# esp8266-01relayfababesp-12-conplanodemas.net
KiCad netlist of a schematic drawn in EAGLE
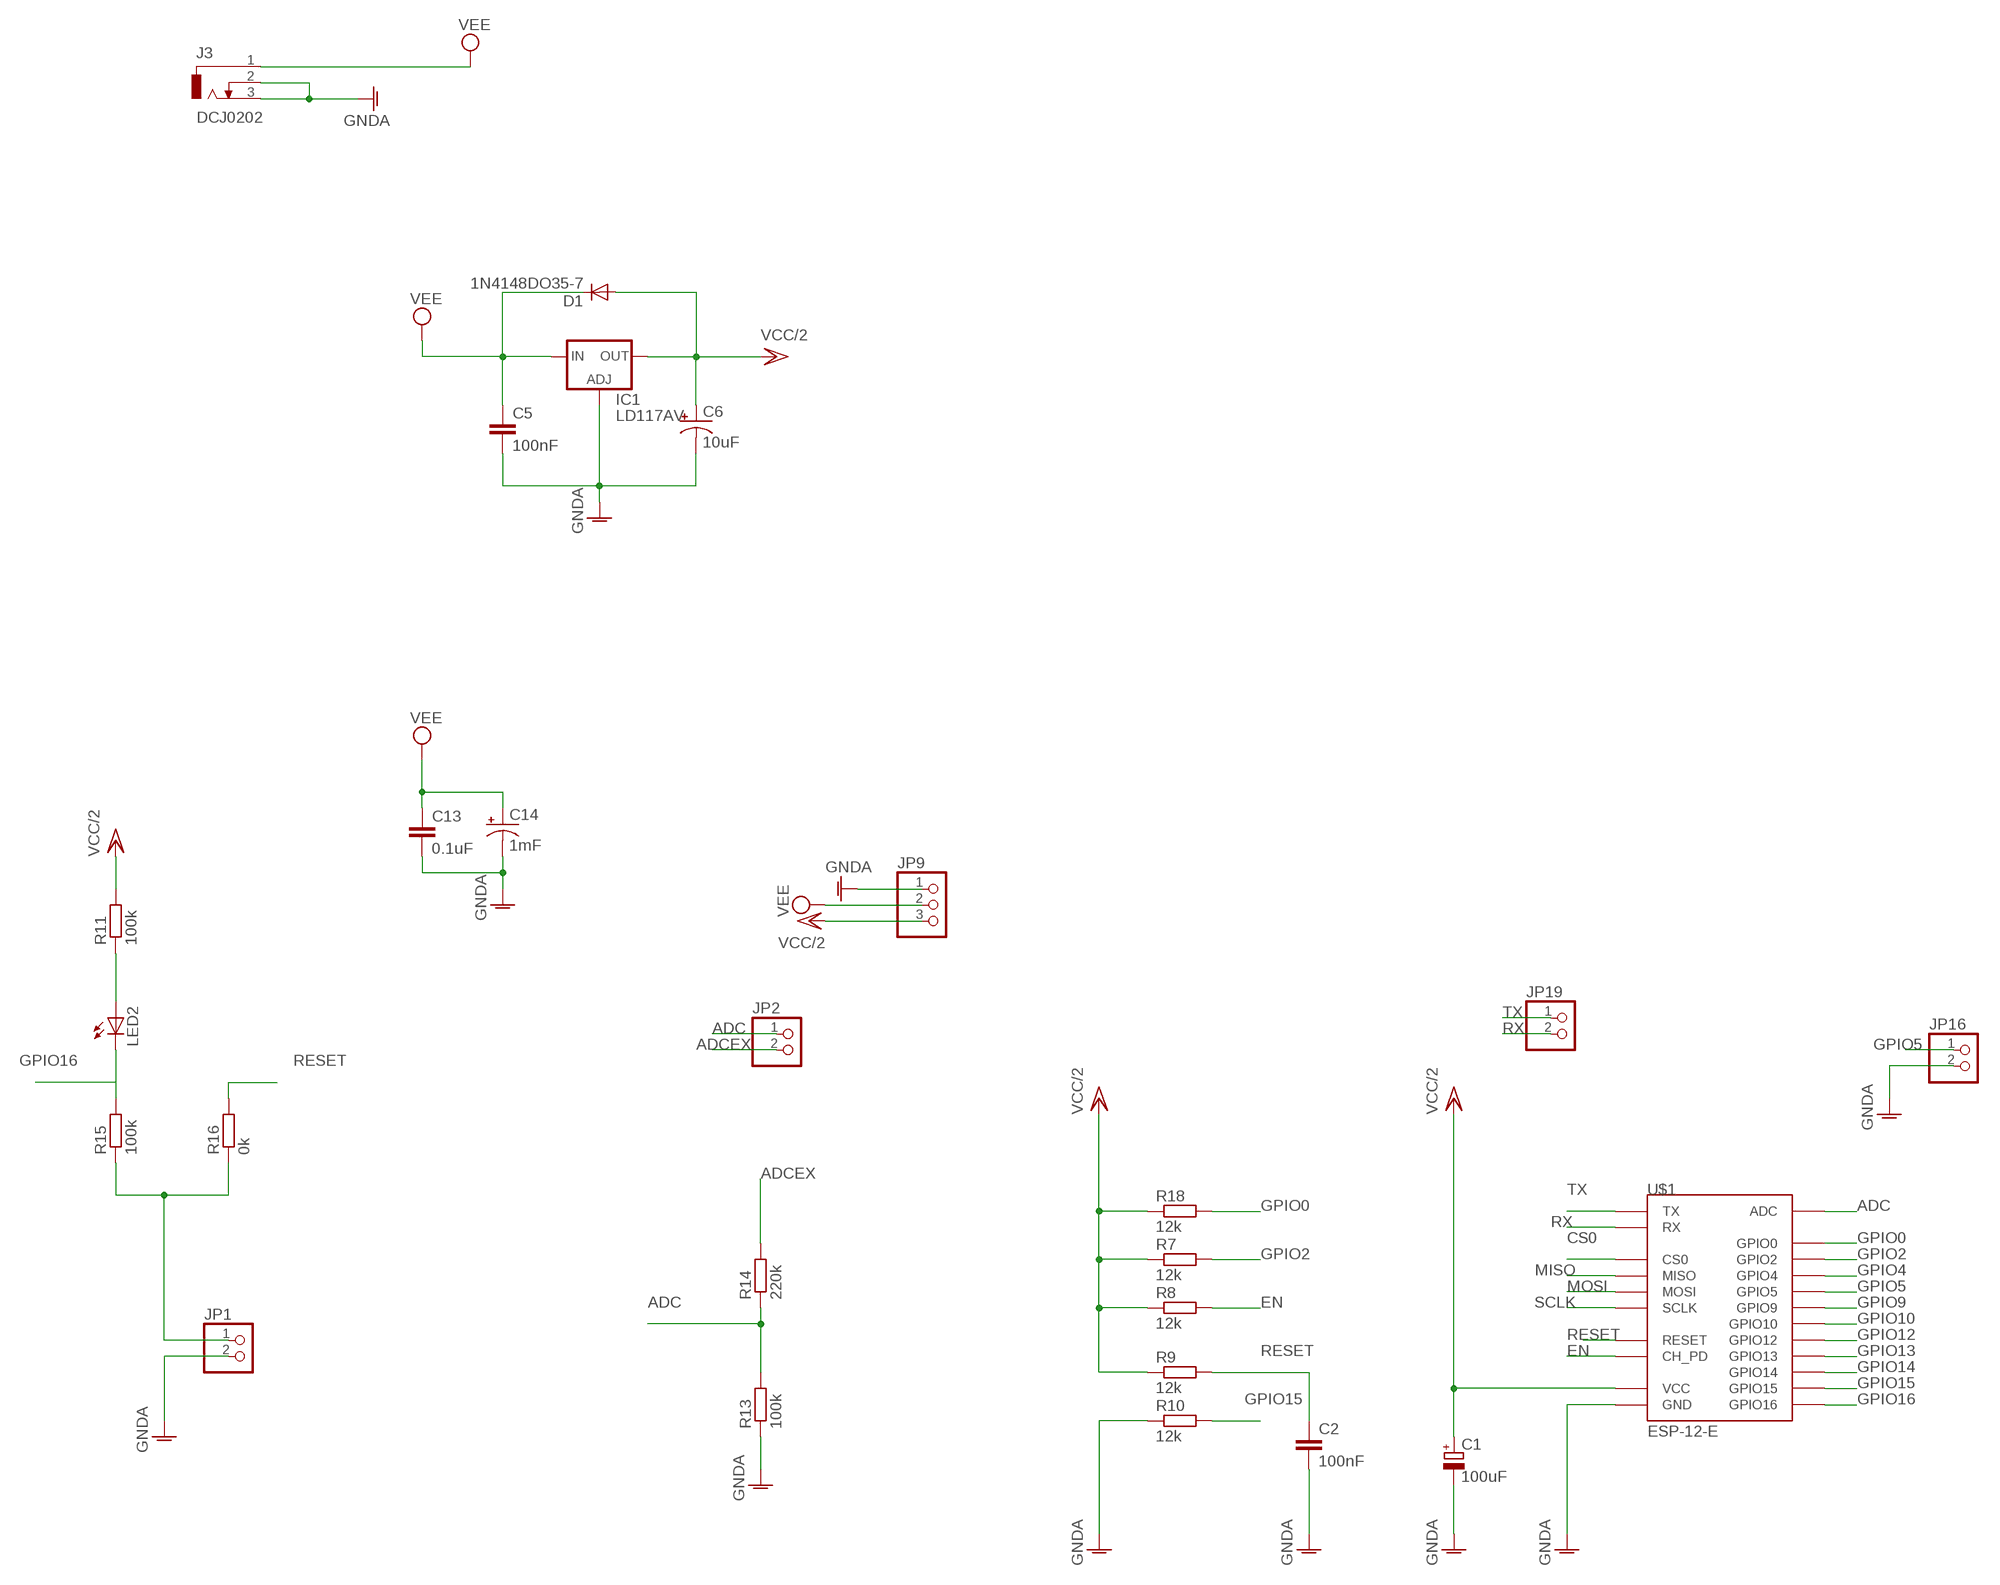
[diagram p0: schematic, sheet 1, part 1 of 2]
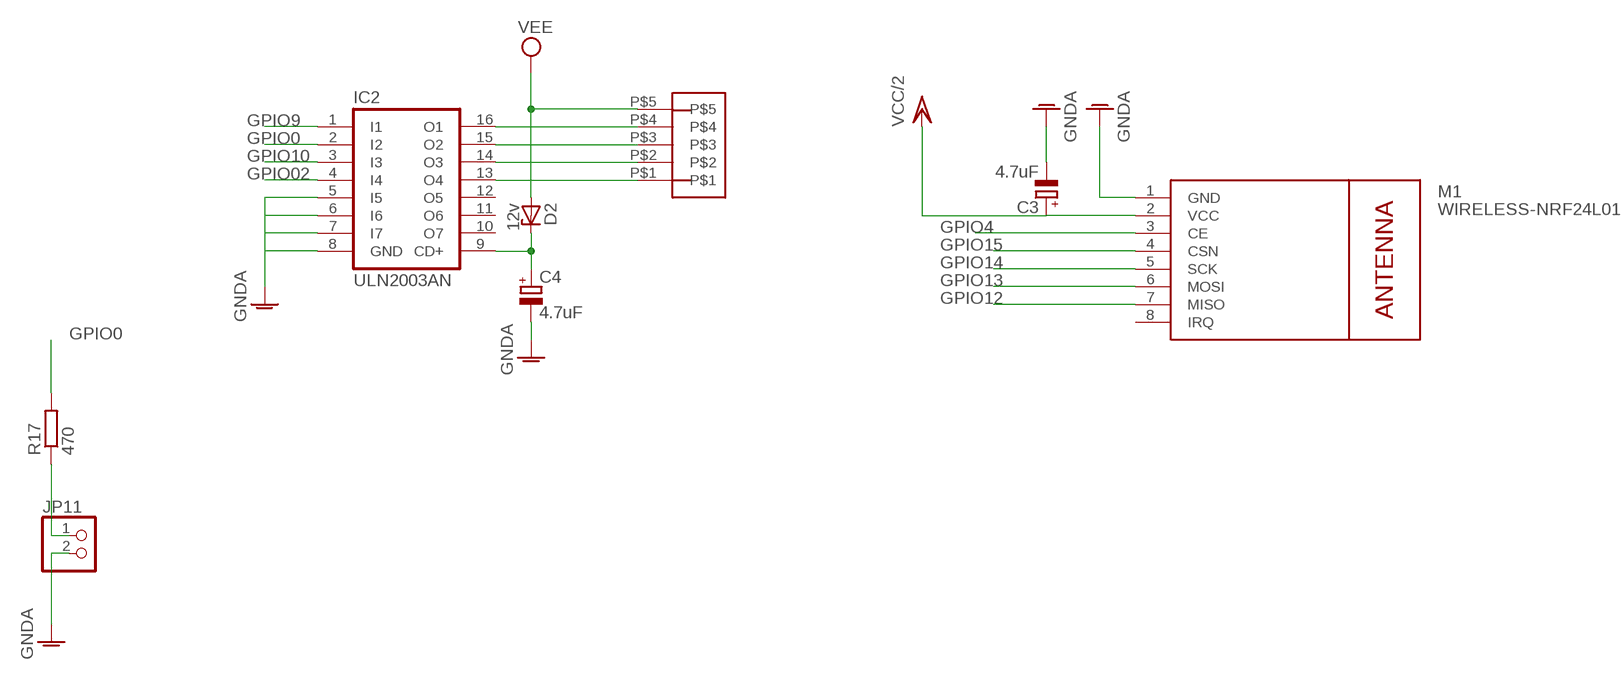
[diagram p1: schematic, sheet 1, part 2 of 2]

(export (version "E")
  (design (tool "Eeschema 10.0.6"))
  (components
    (comp (ref "C1")
      (value "100uF")
      (footprint "eagle-import:TT5D7")
      (libsource (lib "eagle-import") (part "CPOL-EUTT5D7"))
    )
    (comp (ref "C2")
      (value "100nF")
      (footprint "eagle-import:C025-024X044")
      (libsource (lib "eagle-import") (part "C-EU025-024X044"))
    )
    (comp (ref "C3")
      (value "4.7uF")
      (footprint "eagle-import:TT5D7")
      (libsource (lib "eagle-import") (part "CPOL-EUTT5D7"))
    )
    (comp (ref "C4")
      (value "4.7uF")
      (footprint "eagle-import:TT5D7")
      (libsource (lib "eagle-import") (part "CPOL-EUTT5D7"))
    )
    (comp (ref "C5")
      (value "100nF")
      (footprint "eagle-import:C025-025X050")
      (libsource (lib "eagle-import") (part "C-EU025-025X050"))
    )
    (comp (ref "C6")
      (value "10uF")
      (footprint "eagle-import:E2,5-6E")
      (libsource (lib "eagle-import") (part "CPOL-USE2,5-6E"))
    )
    (comp (ref "C13")
      (value "0.1uF")
      (footprint "eagle-import:C025-025X050")
      (libsource (lib "eagle-import") (part "C-EU025-025X050"))
    )
    (comp (ref "C14")
      (value "1mF")
      (footprint "eagle-import:E2,5-6E")
      (libsource (lib "eagle-import") (part "CPOL-USE2,5-6E"))
    )
    (comp (ref "D1")
      (value "1N4148DO35-7")
      (footprint "eagle-import:DO35-7")
      (libsource (lib "eagle-import") (part "1N4148DO35-7"))
    )
    (comp (ref "D2")
      (value "12v")
      (footprint "eagle-import:P1Z12")
      (libsource (lib "eagle-import") (part "ZENER-DIODEP1-12"))
    )
    (comp (ref "IC1")
      (value "LD117AV")
      (footprint "eagle-import:TO220L1")
      (libsource (lib "eagle-import") (part "LD117A?V"))
    )
    (comp (ref "IC2")
      (value "ULN2003AN")
      (footprint "eagle-import:DIL16")
      (libsource (lib "eagle-import") (part "ULN2003AN"))
    )
    (comp (ref "J3")
      (value "DCJ0202")
      (footprint "eagle-import:DCJ0202")
      (libsource (lib "eagle-import") (part "DCJ0202"))
    )
    (comp (ref "JP1")
      (value "PINHD-1X2")
      (footprint "eagle-import:1X02")
      (libsource (lib "eagle-import") (part "PINHD-1X2"))
    )
    (comp (ref "JP2")
      (value "PINHD-1X2")
      (footprint "eagle-import:1X02")
      (libsource (lib "eagle-import") (part "PINHD-1X2"))
    )
    (comp (ref "JP9")
      (value "PINHD-1X3")
      (footprint "eagle-import:1X03")
      (libsource (lib "eagle-import") (part "PINHD-1X3"))
    )
    (comp (ref "JP11")
      (value "PINHD-1X2")
      (footprint "eagle-import:1X02")
      (libsource (lib "eagle-import") (part "PINHD-1X2"))
    )
    (comp (ref "JP16")
      (value "PINHD-1X2")
      (footprint "eagle-import:1X02")
      (libsource (lib "eagle-import") (part "PINHD-1X2"))
    )
    (comp (ref "JP19")
      (value "PINHD-1X2")
      (footprint "eagle-import:1X02")
      (libsource (lib "eagle-import") (part "PINHD-1X2"))
    )
    (comp (ref "LED2")
      (value "LED3MM")
      (footprint "eagle-import:LED3MM")
      (libsource (lib "eagle-import") (part "LED3MM"))
    )
    (comp (ref "M1")
      (value "WIRELESS-NRF24L01")
      (footprint "eagle-import:WIRELESS-NRF24L01")
      (libsource (lib "eagle-import") (part "WIRELESS-NRF24L01"))
    )
    (comp (ref "R7")
      (value "12k")
      (footprint "eagle-import:0207_7")
      (libsource (lib "eagle-import") (part "R-EU_0207/7"))
    )
    (comp (ref "R8")
      (value "12k")
      (footprint "eagle-import:0207_7")
      (libsource (lib "eagle-import") (part "R-EU_0207/7"))
    )
    (comp (ref "R9")
      (value "12k")
      (footprint "eagle-import:0207_7")
      (libsource (lib "eagle-import") (part "R-EU_0207/7"))
    )
    (comp (ref "R10")
      (value "12k")
      (footprint "eagle-import:0207_7")
      (libsource (lib "eagle-import") (part "R-EU_0207/7"))
    )
    (comp (ref "R11")
      (value "100k")
      (footprint "eagle-import:0207_7")
      (libsource (lib "eagle-import") (part "R-EU_0207/7"))
    )
    (comp (ref "R13")
      (value "100k")
      (footprint "eagle-import:0207_7")
      (libsource (lib "eagle-import") (part "R-EU_0207/7"))
    )
    (comp (ref "R14")
      (value "220k")
      (footprint "eagle-import:0207_7")
      (libsource (lib "eagle-import") (part "R-EU_0207/7"))
    )
    (comp (ref "R15")
      (value "100k")
      (footprint "eagle-import:0207_7")
      (libsource (lib "eagle-import") (part "R-EU_0207/7"))
    )
    (comp (ref "R16")
      (value "0k")
      (footprint "eagle-import:0207_7")
      (libsource (lib "eagle-import") (part "R-EU_0207/7"))
    )
    (comp (ref "R17")
      (value "470")
      (footprint "eagle-import:0207_7")
      (libsource (lib "eagle-import") (part "R-EU_0207/7"))
    )
    (comp (ref "R18")
      (value "12k")
      (footprint "eagle-import:0207_7")
      (libsource (lib "eagle-import") (part "R-EU_0207/7"))
    )
    (comp (ref "U$1")
      (value "ESP-12-E")
      (footprint "eagle-import:ESP-12-E")
      (libsource (lib "eagle-import") (part "ESP-12-E"))
    )
    (comp (ref "U$3")
      (value "5_PIN_JST-XH")
      (footprint "eagle-import:5_PIN_JST-XH")
      (libsource (lib "eagle-import") (part "5_PIN_JST-XH"))
    )
  )
  (nets
    (net (code "1") (name "/ADC") (class "Default")
      (node (ref "JP2") (pin "1") (pinfunction "1_1") (pintype "passive"))
      (node (ref "R13") (pin "2") (pinfunction "2_2") (pintype "passive"))
      (node (ref "R14") (pin "1") (pinfunction "1_1") (pintype "passive"))
      (node (ref "U$1") (pin "ADC") (pinfunction "ADC_ADC") (pintype "bidirectional"))
    )
    (net (code "2") (name "/ADCEX") (class "Default")
      (node (ref "JP2") (pin "2") (pinfunction "2_2") (pintype "passive"))
      (node (ref "R14") (pin "2") (pinfunction "2_2") (pintype "passive"))
    )
    (net (code "3") (name "/CS0") (class "Default")
      (node (ref "U$1") (pin "CS0") (pinfunction "CS0_CS0") (pintype "bidirectional"))
    )
    (net (code "4") (name "/EN") (class "Default")
      (node (ref "R8") (pin "2") (pinfunction "2_2") (pintype "passive"))
      (node (ref "U$1") (pin "CH_PD") (pinfunction "CH_PD_CH_PD") (pintype "bidirectional"))
    )
    (net (code "5") (name "/GPIO0") (class "Default")
      (node (ref "IC2") (pin "2") (pinfunction "I2_2") (pintype "input"))
      (node (ref "R17") (pin "2") (pinfunction "2_2") (pintype "passive"))
      (node (ref "R18") (pin "2") (pinfunction "2_2") (pintype "passive"))
      (node (ref "U$1") (pin "GPIO0") (pinfunction "GPIO0_GPIO0") (pintype "bidirectional"))
    )
    (net (code "6") (name "/GPIO2") (class "Default")
      (node (ref "R7") (pin "2") (pinfunction "2_2") (pintype "passive"))
      (node (ref "U$1") (pin "GPIO2") (pinfunction "GPIO2_GPIO2") (pintype "bidirectional"))
    )
    (net (code "7") (name "/GPIO02") (class "Default")
      (node (ref "IC2") (pin "4") (pinfunction "I4_4") (pintype "input"))
    )
    (net (code "8") (name "/GPIO4") (class "Default")
      (node (ref "M1") (pin "3") (pinfunction "CE_3") (pintype "bidirectional"))
      (node (ref "U$1") (pin "GPIO4") (pinfunction "GPIO4_GPIO4") (pintype "bidirectional"))
    )
    (net (code "9") (name "/GPIO5") (class "Default")
      (node (ref "JP16") (pin "1") (pinfunction "1_1") (pintype "passive"))
      (node (ref "U$1") (pin "GPIO5") (pinfunction "GPIO5_GPIO5") (pintype "bidirectional"))
    )
    (net (code "10") (name "/GPIO9") (class "Default")
      (node (ref "IC2") (pin "1") (pinfunction "I1_1") (pintype "input"))
      (node (ref "U$1") (pin "GPIO9") (pinfunction "GPIO9_GPIO9") (pintype "bidirectional"))
    )
    (net (code "11") (name "/GPIO10") (class "Default")
      (node (ref "IC2") (pin "3") (pinfunction "I3_3") (pintype "input"))
      (node (ref "U$1") (pin "GPIO10") (pinfunction "GPIO10_GPIO10") (pintype "bidirectional"))
    )
    (net (code "12") (name "/GPIO12") (class "Default")
      (node (ref "M1") (pin "7") (pinfunction "MISO_7") (pintype "bidirectional"))
      (node (ref "U$1") (pin "GPIO12") (pinfunction "GPIO12_GPIO12") (pintype "bidirectional"))
    )
    (net (code "13") (name "/GPIO13") (class "Default")
      (node (ref "M1") (pin "6") (pinfunction "MOSI_6") (pintype "bidirectional"))
      (node (ref "U$1") (pin "GPIO13") (pinfunction "GPIO13_GPIO13") (pintype "bidirectional"))
    )
    (net (code "14") (name "/GPIO14") (class "Default")
      (node (ref "M1") (pin "5") (pinfunction "SCK_5") (pintype "bidirectional"))
      (node (ref "U$1") (pin "GPIO14") (pinfunction "GPIO14_GPIO14") (pintype "bidirectional"))
    )
    (net (code "15") (name "/GPIO15") (class "Default")
      (node (ref "M1") (pin "4") (pinfunction "CSN_4") (pintype "bidirectional"))
      (node (ref "R10") (pin "2") (pinfunction "2_2") (pintype "passive"))
      (node (ref "U$1") (pin "GPIO15") (pinfunction "GPIO15_GPIO15") (pintype "bidirectional"))
    )
    (net (code "16") (name "/GPIO16") (class "Default")
      (node (ref "LED2") (pin "K") (pinfunction "C_K") (pintype "passive"))
      (node (ref "R15") (pin "2") (pinfunction "2_2") (pintype "passive"))
      (node (ref "U$1") (pin "GPIO16") (pinfunction "GPIO16_GPIO16") (pintype "bidirectional"))
    )
    (net (code "17") (name "/MISO") (class "Default")
      (node (ref "U$1") (pin "MISO") (pinfunction "MISO_MISO") (pintype "bidirectional"))
    )
    (net (code "18") (name "/MOSI") (class "Default")
      (node (ref "U$1") (pin "MOSI") (pinfunction "MOSI_MOSI") (pintype "bidirectional"))
    )
    (net (code "19") (name "/RESET") (class "Default")
      (node (ref "C2") (pin "1") (pinfunction "1_1") (pintype "passive"))
      (node (ref "R16") (pin "2") (pinfunction "2_2") (pintype "passive"))
      (node (ref "R9") (pin "2") (pinfunction "2_2") (pintype "passive"))
      (node (ref "U$1") (pin "RESET") (pinfunction "RESET_RESET") (pintype "bidirectional"))
    )
    (net (code "20") (name "/RX") (class "Default")
      (node (ref "JP19") (pin "2") (pinfunction "2_2") (pintype "passive"))
      (node (ref "U$1") (pin "RX") (pinfunction "RX_RX") (pintype "bidirectional"))
    )
    (net (code "21") (name "/SCLK") (class "Default")
      (node (ref "U$1") (pin "SCLK") (pinfunction "SCLK_SCLK") (pintype "bidirectional"))
    )
    (net (code "22") (name "/TX") (class "Default")
      (node (ref "JP19") (pin "1") (pinfunction "1_1") (pintype "passive"))
      (node (ref "U$1") (pin "TX") (pinfunction "TX_TX") (pintype "bidirectional"))
    )
    (net (code "23") (name "GNDA") (class "Default")
      (node (ref "C1") (pin "-") (pinfunction "-_-") (pintype "passive"))
      (node (ref "C13") (pin "2") (pinfunction "2_2") (pintype "passive"))
      (node (ref "C14") (pin "-") (pinfunction "-_-") (pintype "passive"))
      (node (ref "C2") (pin "2") (pinfunction "2_2") (pintype "passive"))
      (node (ref "C3") (pin "-") (pinfunction "-_-") (pintype "passive"))
      (node (ref "C4") (pin "-") (pinfunction "-_-") (pintype "passive"))
      (node (ref "C5") (pin "2") (pinfunction "2_2") (pintype "passive"))
      (node (ref "C6") (pin "-") (pinfunction "-_-") (pintype "passive"))
      (node (ref "IC1") (pin "1") (pinfunction "ADJ_1") (pintype "input"))
      (node (ref "IC2") (pin "5") (pinfunction "I5_5") (pintype "input"))
      (node (ref "IC2") (pin "6") (pinfunction "I6_6") (pintype "input"))
      (node (ref "IC2") (pin "7") (pinfunction "I7_7") (pintype "input"))
      (node (ref "IC2") (pin "8") (pinfunction "GND_8") (pintype "power_in"))
      (node (ref "J3") (pin "2") (pinfunction "2_2") (pintype "passive"))
      (node (ref "J3") (pin "3") (pinfunction "3_3") (pintype "passive"))
      (node (ref "JP1") (pin "2") (pinfunction "2_2") (pintype "passive"))
      (node (ref "JP11") (pin "2") (pinfunction "2_2") (pintype "passive"))
      (node (ref "JP16") (pin "2") (pinfunction "2_2") (pintype "passive"))
      (node (ref "JP9") (pin "1") (pinfunction "1_1") (pintype "passive"))
      (node (ref "M1") (pin "1") (pinfunction "GND_1") (pintype "power_in"))
      (node (ref "R10") (pin "1") (pinfunction "1_1") (pintype "passive"))
      (node (ref "R13") (pin "1") (pinfunction "1_1") (pintype "passive"))
      (node (ref "U$1") (pin "GND") (pinfunction "GND_GND") (pintype "bidirectional"))
    )
    (net (code "24") (name "Net-(IC2-CD+)") (class "Default")
      (node (ref "C4") (pin "+") (pinfunction "+_+") (pintype "passive"))
      (node (ref "D2") (pin "C") (pinfunction "C_C") (pintype "passive"))
      (node (ref "IC2") (pin "9") (pinfunction "CD+_9") (pintype "passive"))
    )
    (net (code "25") (name "Net-(IC2-O1)") (class "Default")
      (node (ref "IC2") (pin "16") (pinfunction "O1_16") (pintype "open_collector"))
      (node (ref "U$3") (pin "P$4") (pinfunction "P$4_P$4") (pintype "bidirectional"))
    )
    (net (code "26") (name "Net-(IC2-O2)") (class "Default")
      (node (ref "IC2") (pin "15") (pinfunction "O2_15") (pintype "open_collector"))
      (node (ref "U$3") (pin "P$3") (pinfunction "P$3_P$3") (pintype "bidirectional"))
    )
    (net (code "27") (name "Net-(IC2-O3)") (class "Default")
      (node (ref "IC2") (pin "14") (pinfunction "O3_14") (pintype "open_collector"))
      (node (ref "U$3") (pin "P$2") (pinfunction "P$2_P$2") (pintype "bidirectional"))
    )
    (net (code "28") (name "Net-(IC2-O4)") (class "Default")
      (node (ref "IC2") (pin "13") (pinfunction "O4_13") (pintype "open_collector"))
      (node (ref "U$3") (pin "P$1") (pinfunction "P$1_P$1") (pintype "bidirectional"))
    )
    (net (code "29") (name "Net-(JP1-Pad1)") (class "Default")
      (node (ref "JP1") (pin "1") (pinfunction "1_1") (pintype "passive"))
      (node (ref "R15") (pin "1") (pinfunction "1_1") (pintype "passive"))
      (node (ref "R16") (pin "1") (pinfunction "1_1") (pintype "passive"))
    )
    (net (code "30") (name "Net-(JP11-Pad1)") (class "Default")
      (node (ref "JP11") (pin "1") (pinfunction "1_1") (pintype "passive"))
      (node (ref "R17") (pin "1") (pinfunction "1_1") (pintype "passive"))
    )
    (net (code "31") (name "Net-(LED2-PadA)") (class "Default")
      (node (ref "LED2") (pin "A") (pinfunction "A_A") (pintype "passive"))
      (node (ref "R11") (pin "1") (pinfunction "1_1") (pintype "passive"))
    )
    (net (code "32") (name "VCC{slash}2") (class "Default")
      (node (ref "C1") (pin "+") (pinfunction "+_+") (pintype "passive"))
      (node (ref "C3") (pin "+") (pinfunction "+_+") (pintype "passive"))
      (node (ref "C6") (pin "+") (pinfunction "+_+") (pintype "passive"))
      (node (ref "D1") (pin "A") (pinfunction "A_A") (pintype "passive"))
      (node (ref "IC1") (pin "2") (pinfunction "OUT_2") (pintype "passive"))
      (node (ref "JP9") (pin "3") (pinfunction "3_3") (pintype "passive"))
      (node (ref "M1") (pin "2") (pinfunction "VCC_2") (pintype "power_in"))
      (node (ref "R11") (pin "2") (pinfunction "2_2") (pintype "passive"))
      (node (ref "R18") (pin "1") (pinfunction "1_1") (pintype "passive"))
      (node (ref "R7") (pin "1") (pinfunction "1_1") (pintype "passive"))
      (node (ref "R8") (pin "1") (pinfunction "1_1") (pintype "passive"))
      (node (ref "R9") (pin "1") (pinfunction "1_1") (pintype "passive"))
      (node (ref "U$1") (pin "VCC") (pinfunction "VCC_VCC") (pintype "bidirectional"))
    )
    (net (code "33") (name "VEE") (class "Default")
      (node (ref "C13") (pin "1") (pinfunction "1_1") (pintype "passive"))
      (node (ref "C14") (pin "+") (pinfunction "+_+") (pintype "passive"))
      (node (ref "C5") (pin "1") (pinfunction "1_1") (pintype "passive"))
      (node (ref "D1") (pin "C") (pinfunction "C_C") (pintype "passive"))
      (node (ref "D2") (pin "A") (pinfunction "A_A") (pintype "passive"))
      (node (ref "IC1") (pin "3") (pinfunction "IN_3") (pintype "input"))
      (node (ref "J3") (pin "1") (pinfunction "1_1") (pintype "passive"))
      (node (ref "JP9") (pin "2") (pinfunction "2_2") (pintype "passive"))
      (node (ref "U$3") (pin "P$5") (pinfunction "P$5_P$5") (pintype "bidirectional"))
    )
    (net (code "34") (name "unconnected-(IC2-O5-Pad12)") (class "Default")
      (node (ref "IC2") (pin "12") (pinfunction "O5_12") (pintype "open_collector"))
    )
    (net (code "35") (name "unconnected-(IC2-O6-Pad11)") (class "Default")
      (node (ref "IC2") (pin "11") (pinfunction "O6_11") (pintype "open_collector"))
    )
    (net (code "36") (name "unconnected-(IC2-O7-Pad10)") (class "Default")
      (node (ref "IC2") (pin "10") (pinfunction "O7_10") (pintype "open_collector"))
    )
    (net (code "37") (name "unconnected-(M1-IRQ-Pad8)") (class "Default")
      (node (ref "M1") (pin "8") (pinfunction "IRQ_8") (pintype "bidirectional"))
    )
  )
)
